# Potentiometer.net
KiCad netlist of a schematic drawn in Altium Designer
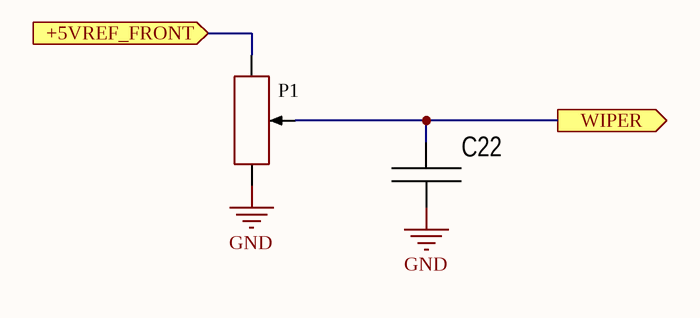
[diagram p0: Potentiometer.SchDoc]

(export (version "E")
  (design (tool "Eeschema 10.0.6"))
  (components
    (comp (ref "C22")
      (value "~")
      (footprint "StandardCase:CAP: 1206")
      (fields
        (field (name "MANUFACTURER") "Yageo")
        (field (name "PARTNUMBER") "CC1206KRX7R9BB104")
        (field (name "VALUEMANUFACTURERPARTNUMBER") "Ceramic capacitor, 0.1μF, 1206")
      )
      (libsource (lib "Capacitor") (part "Ceramic_1206"))
    )
    (comp (ref "P1")
      (value "~")
      (footprint "FP_lib_PCB:СП4-2МА")
      (fields (field (name "VALUEMANUFACTURERPARTNUMBER") "СП4-2МА"))
      (libsource (lib "FP_lib_SCH") (part "СП4-2МА"))
    )
  )
  (nets
    (net (code "1") (name "/+5VREF_FRONT") (class "Default")
      (node (ref "P1") (pin "3") (pinfunction "CW_3") (pintype "passive"))
    )
    (net (code "2") (name "/WIPER") (class "Default")
      (node (ref "C22") (pin "2") (pinfunction "2_2") (pintype "power_in"))
      (node (ref "P1") (pin "2") (pinfunction "2_2") (pintype "passive"))
    )
    (net (code "3") (name "GND") (class "Default")
      (node (ref "C22") (pin "1") (pinfunction "1_1") (pintype "power_in"))
      (node (ref "P1") (pin "1") (pinfunction "CCW_1") (pintype "passive"))
    )
  )
)
